# Storage.net
KiCad netlist of a schematic drawn in Altium Designer
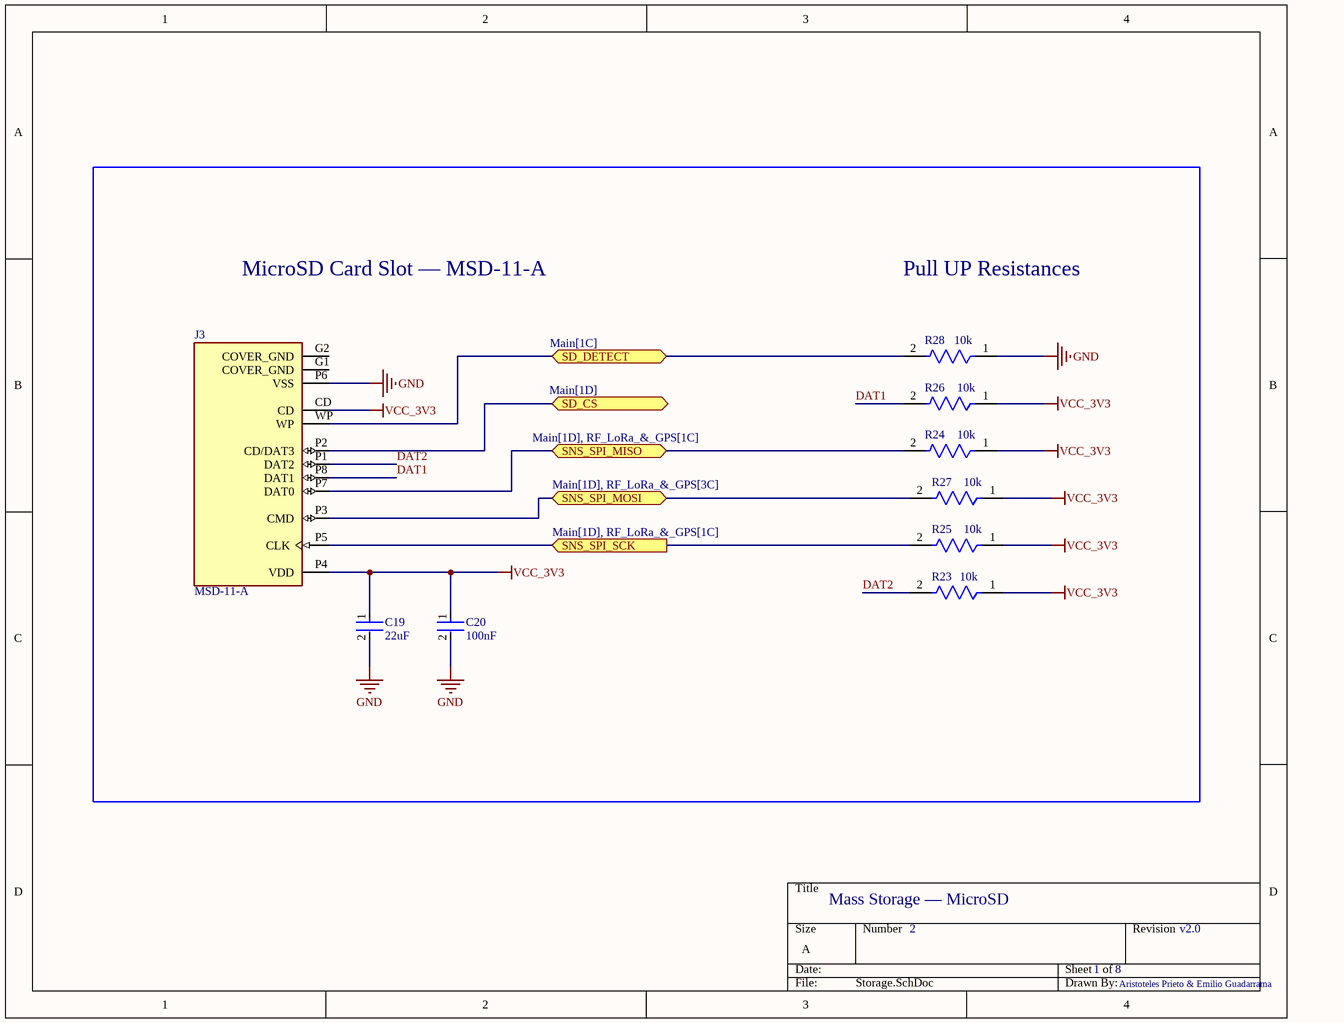
[diagram p0: Storage.SchDoc]

(export (version "E")
  (design (tool "Eeschema 10.0.6"))
  (components
    (comp (ref "C19")
      (value "22uF")
      (footprint "FP-C0805C-DN-MFG")
      (description "CAP CER 0.1UF 50V X7R 0805")
      (fields
        (field (name "MANUFACTURER PART NUMBER") "C0805C104K5RACTU")
        (field (name "MANUFACTURER") "KEMET")
      )
      (libsource (lib "Altium Content Vault") (part "b4654b650e69147ec39a6b967a45e02"))
    )
    (comp (ref "C20")
      (value "100nF")
      (footprint "FP-C0805C-DN-MFG")
      (description "CAP CER 0.1UF 50V X7R 0805")
      (fields
        (field (name "MANUFACTURER PART NUMBER") "C0805C104K5RACTU")
        (field (name "MANUFACTURER") "KEMET")
      )
      (libsource (lib "Altium Content Vault") (part "b4654b650e69147ec39a6b967a45e02"))
    )
    (comp (ref "J3")
      (value "MSD-11-A")
      (footprint "CUI_MSD-11-A")
      (fields (field (name "MF") "Same Sky"))
      (libsource (lib "SD_Holder-MSD-11-A") (part "MSD-11-A"))
    )
    (comp (ref "R23")
      (value "10k")
      (footprint "FP-MCT0603-IPC_A")
      (description "RES SMD 100 OHM 1% 1/8W 0603")
      (fields (field (name "TOLERANCE") "0.1%"))
      (libsource (lib "Altium Content Vault") (part "1029c3af85768c4190bb7ad29bc67b5"))
    )
    (comp (ref "R24")
      (value "10k")
      (footprint "FP-MCT0603-IPC_A")
      (description "RES SMD 100 OHM 1% 1/8W 0603")
      (fields (field (name "TOLERANCE") "0.1%"))
      (libsource (lib "Altium Content Vault") (part "1029c3af85768c4190bb7ad29bc67b5"))
    )
    (comp (ref "R25")
      (value "10k")
      (footprint "FP-MCT0603-IPC_A")
      (description "RES SMD 100 OHM 1% 1/8W 0603")
      (fields (field (name "TOLERANCE") "0.1%"))
      (libsource (lib "Altium Content Vault") (part "1029c3af85768c4190bb7ad29bc67b5"))
    )
    (comp (ref "R26")
      (value "10k")
      (footprint "FP-MCT0603-IPC_A")
      (description "RES SMD 100 OHM 1% 1/8W 0603")
      (fields (field (name "TOLERANCE") "0.1%"))
      (libsource (lib "Altium Content Vault") (part "1029c3af85768c4190bb7ad29bc67b5"))
    )
    (comp (ref "R27")
      (value "10k")
      (footprint "FP-MCT0603-IPC_A")
      (description "RES SMD 100 OHM 1% 1/8W 0603")
      (fields (field (name "TOLERANCE") "0.1%"))
      (libsource (lib "Altium Content Vault") (part "1029c3af85768c4190bb7ad29bc67b5"))
    )
    (comp (ref "R28")
      (value "10k")
      (footprint "FP-MCT0603-IPC_A")
      (description "RES SMD 100 OHM 1% 1/8W 0603")
      (fields (field (name "TOLERANCE") "0.1%"))
      (libsource (lib "Altium Content Vault") (part "1029c3af85768c4190bb7ad29bc67b5"))
    )
  )
  (nets
    (net (code "1") (name "/DAT1") (class "Default")
      (node (ref "J3") (pin "P8") (pinfunction "DAT1_P8") (pintype "bidirectional"))
      (node (ref "R26") (pin "2") (pinfunction "2_2") (pintype "passive"))
    )
    (net (code "2") (name "/DAT2") (class "Default")
      (node (ref "J3") (pin "P1") (pinfunction "DAT2_P1") (pintype "bidirectional"))
      (node (ref "R23") (pin "2") (pinfunction "2_2") (pintype "passive"))
    )
    (net (code "3") (name "/SD_CS") (class "Default")
      (node (ref "J3") (pin "P2") (pinfunction "CD/DAT3_P2") (pintype "bidirectional"))
    )
    (net (code "4") (name "/SD_DETECT") (class "Default")
      (node (ref "J3") (pin "WP") (pinfunction "WP_WP") (pintype "passive"))
      (node (ref "R28") (pin "2") (pinfunction "2_2") (pintype "passive"))
    )
    (net (code "5") (name "/SNS_SPI_MISO") (class "Default")
      (node (ref "J3") (pin "P7") (pinfunction "DAT0_P7") (pintype "bidirectional"))
      (node (ref "R24") (pin "2") (pinfunction "2_2") (pintype "passive"))
    )
    (net (code "6") (name "/SNS_SPI_MOSI") (class "Default")
      (node (ref "J3") (pin "P3") (pinfunction "CMD_P3") (pintype "bidirectional"))
      (node (ref "R27") (pin "2") (pinfunction "2_2") (pintype "passive"))
    )
    (net (code "7") (name "/SNS_SPI_SCK") (class "Default")
      (node (ref "J3") (pin "P5") (pinfunction "CLK_P5") (pintype "input"))
      (node (ref "R25") (pin "2") (pinfunction "2_2") (pintype "passive"))
    )
    (net (code "8") (name "GND") (class "Default")
      (node (ref "C19") (pin "2") (pinfunction "2_2") (pintype "passive"))
      (node (ref "C20") (pin "2") (pinfunction "2_2") (pintype "passive"))
      (node (ref "J3") (pin "P6") (pinfunction "VSS_P6") (pintype "power_in"))
      (node (ref "R28") (pin "1") (pinfunction "1_1") (pintype "passive"))
    )
    (net (code "9") (name "VCC_3V3") (class "Default")
      (node (ref "C19") (pin "1") (pinfunction "1_1") (pintype "passive"))
      (node (ref "C20") (pin "1") (pinfunction "1_1") (pintype "passive"))
      (node (ref "J3") (pin "CD") (pinfunction "CD_CD") (pintype "passive"))
      (node (ref "J3") (pin "P4") (pinfunction "VDD_P4") (pintype "power_in"))
      (node (ref "R23") (pin "1") (pinfunction "1_1") (pintype "passive"))
      (node (ref "R24") (pin "1") (pinfunction "1_1") (pintype "passive"))
      (node (ref "R25") (pin "1") (pinfunction "1_1") (pintype "passive"))
      (node (ref "R26") (pin "1") (pinfunction "1_1") (pintype "passive"))
      (node (ref "R27") (pin "1") (pinfunction "1_1") (pintype "passive"))
    )
    (net (code "10") (name "unconnected-(J3-COVER_GND-PadG1)") (class "Default")
      (node (ref "J3") (pin "G1") (pinfunction "COVER_GND_G1") (pintype "power_in"))
    )
    (net (code "11") (name "unconnected-(J3-COVER_GND-PadG2)") (class "Default")
      (node (ref "J3") (pin "G2") (pinfunction "COVER_GND_G2") (pintype "power_in"))
    )
  )
)
